# Tomo5.net
KiCad netlist of a schematic drawn in EAGLE
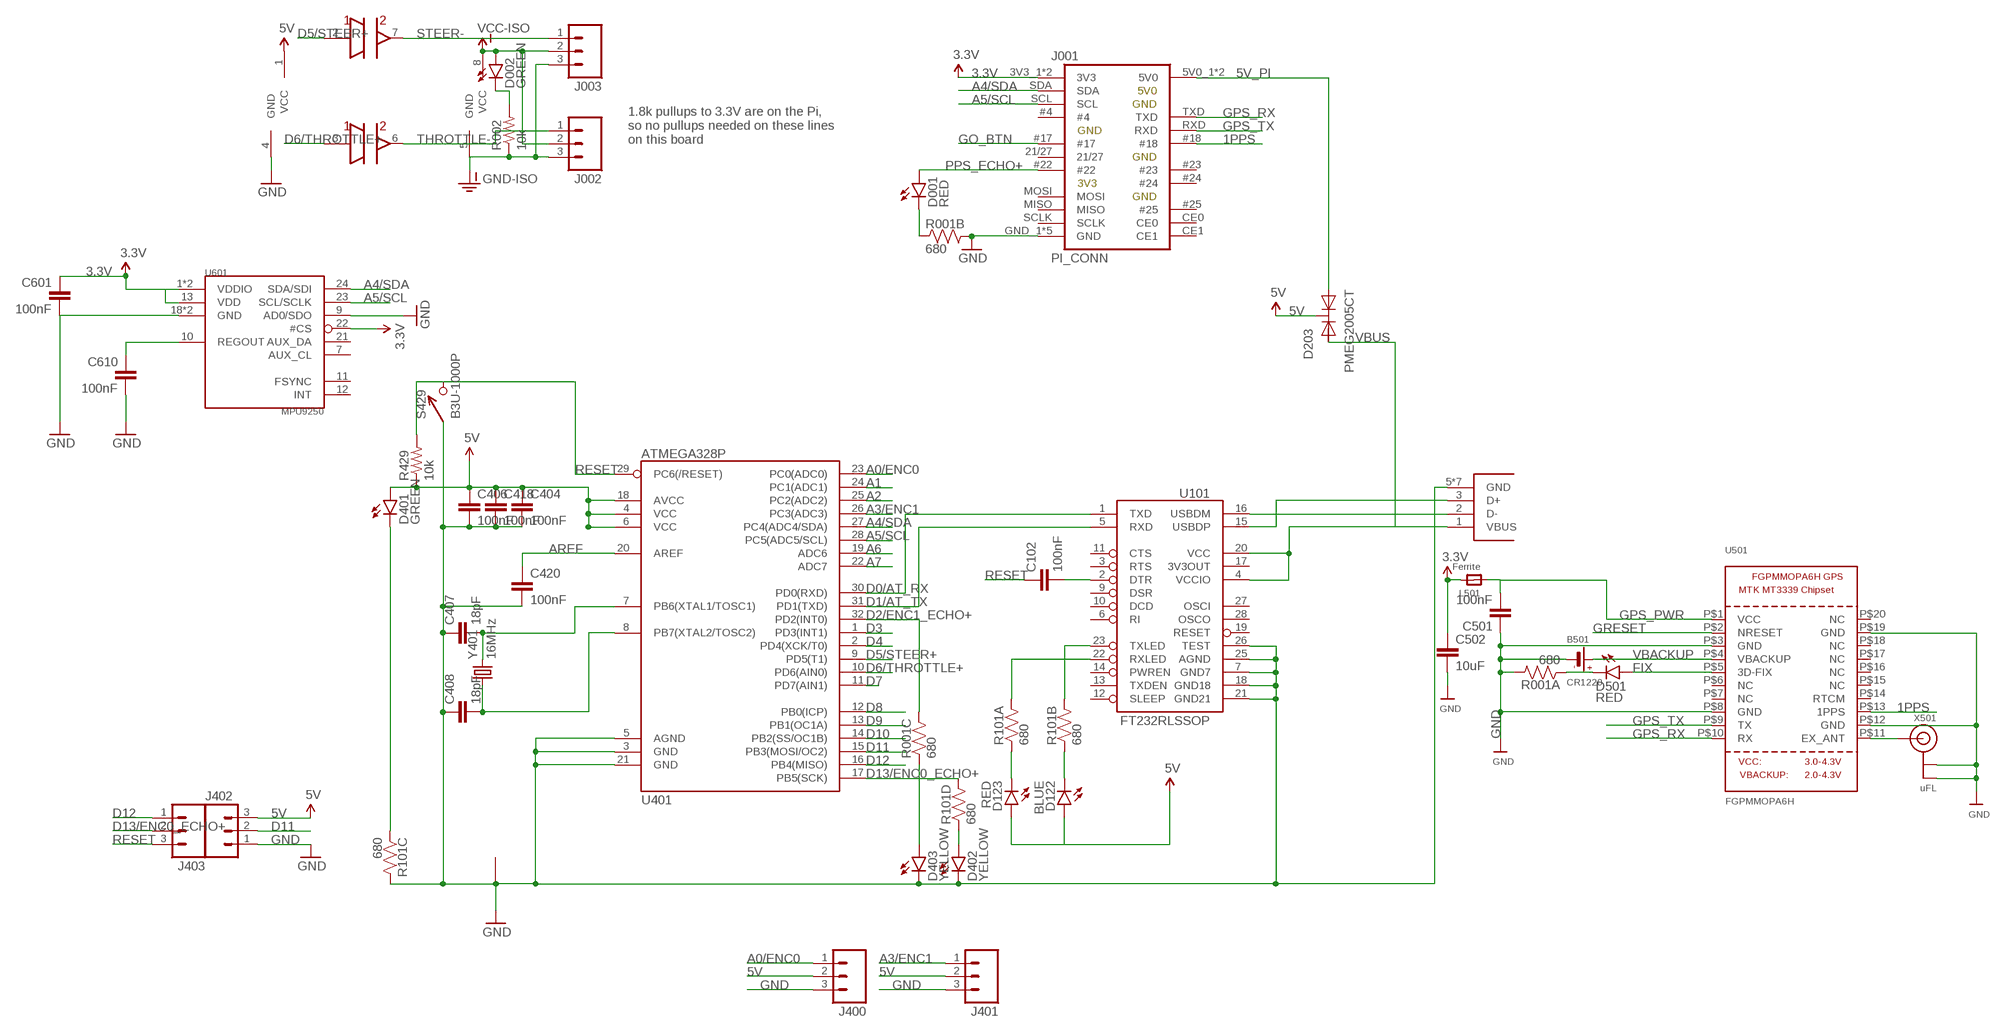
[diagram p0: schematic, sheet 1]

(export (version "E")
  (design (tool "Eeschema 10.0.6"))
  (components
    (comp (ref "B501")
      (value "CR1220")
      (footprint "eagle-import:CR1220-2")
      (libsource (lib "eagle-import") (part "BATTERYCR1220_2"))
    )
    (comp (ref "C102")
      (value "100nF")
      (footprint "eagle-import:0402-CAP")
      (libsource (lib "eagle-import") (part "CAP0402-CAP"))
    )
    (comp (ref "C404")
      (value "100nF")
      (footprint "eagle-import:0402-CAP")
      (libsource (lib "eagle-import") (part "CAP0402-CAP"))
    )
    (comp (ref "C406")
      (value "100nF")
      (footprint "eagle-import:0402-CAP")
      (libsource (lib "eagle-import") (part "CAP0402-CAP"))
    )
    (comp (ref "C407")
      (value "18pF")
      (footprint "eagle-import:0402-CAP")
      (libsource (lib "eagle-import") (part "CAP0402-CAP"))
    )
    (comp (ref "C408")
      (value "18pF")
      (footprint "eagle-import:0402-CAP")
      (libsource (lib "eagle-import") (part "CAP0402-CAP"))
    )
    (comp (ref "C418")
      (value "100nF")
      (footprint "eagle-import:0402-CAP")
      (libsource (lib "eagle-import") (part "CAP0402-CAP"))
    )
    (comp (ref "C420")
      (value "100nF")
      (footprint "eagle-import:0402-CAP")
      (libsource (lib "eagle-import") (part "CAP0402-CAP"))
    )
    (comp (ref "C501")
      (value "100nF")
      (footprint "eagle-import:0402-CAP")
      (libsource (lib "eagle-import") (part "CAP0402-CAP"))
    )
    (comp (ref "C502")
      (value "10uF")
      (footprint "eagle-import:1206")
      (libsource (lib "eagle-import") (part "SparkFun-Capacitors_CAP1206"))
    )
    (comp (ref "C601")
      (value "100nF")
      (footprint "eagle-import:0603-CAP")
      (libsource (lib "eagle-import") (part "0.1UF-25V(+80/-20%)(0603)"))
    )
    (comp (ref "C610")
      (value "100nF")
      (footprint "eagle-import:0402-CAP")
      (libsource (lib "eagle-import") (part "SparkFun-Capacitors_CAP0402-CAP"))
    )
    (comp (ref "D001")
      (value "RED")
      (footprint "eagle-import:LED-0603")
      (libsource (lib "eagle-import") (part "LED0603"))
    )
    (comp (ref "D002")
      (value "GREEN")
      (footprint "eagle-import:LED-0603")
      (libsource (lib "eagle-import") (part "LED0603"))
    )
    (comp (ref "D122")
      (value "BLUE")
      (footprint "eagle-import:LED-0603")
      (libsource (lib "eagle-import") (part "LED0603"))
    )
    (comp (ref "D123")
      (value "RED")
      (footprint "eagle-import:LED-0603")
      (libsource (lib "eagle-import") (part "LED0603"))
    )
    (comp (ref "D203")
      (value "PMEG2005CT")
      (footprint "eagle-import:SOT-23-3")
      (libsource (lib "eagle-import") (part "DIODE_COMMON_CATHODEPMEG2005CT"))
    )
    (comp (ref "D401")
      (value "GREEN")
      (footprint "eagle-import:LED-0603")
      (libsource (lib "eagle-import") (part "LED0603"))
    )
    (comp (ref "D402")
      (value "YELLOW")
      (footprint "eagle-import:LED-0603")
      (libsource (lib "eagle-import") (part "LED0603"))
    )
    (comp (ref "D403")
      (value "YELLOW")
      (footprint "eagle-import:LED-0603")
      (libsource (lib "eagle-import") (part "LED0603"))
    )
    (comp (ref "D501")
      (value "RED")
      (footprint "eagle-import:LED-0603")
      (libsource (lib "eagle-import") (part "LED0603"))
    )
    (comp (ref "J001")
      (value "PI_CONN")
      (footprint "eagle-import:PI_CONN")
      (libsource (lib "eagle-import") (part "PI_CONN"))
    )
    (comp (ref "J002")
      (value "M03PTH")
      (footprint "eagle-import:1X03")
      (libsource (lib "eagle-import") (part "M03PTH"))
    )
    (comp (ref "J003")
      (value "M03PTH")
      (footprint "eagle-import:1X03")
      (libsource (lib "eagle-import") (part "M03PTH"))
    )
    (comp (ref "J101")
      (value "USB_MICROB_JST")
      (footprint "eagle-import:UB-MC5BR3-SD204-4S")
      (libsource (lib "eagle-import") (part "USB_MICROB_JST"))
    )
    (comp (ref "J400")
      (value "M03PTH")
      (footprint "eagle-import:1X03")
      (libsource (lib "eagle-import") (part "M03PTH"))
    )
    (comp (ref "J401")
      (value "M03PTH")
      (footprint "eagle-import:1X03")
      (libsource (lib "eagle-import") (part "M03PTH"))
    )
    (comp (ref "J402")
      (value "M03PTH")
      (footprint "eagle-import:1X03")
      (libsource (lib "eagle-import") (part "M03PTH"))
    )
    (comp (ref "J403")
      (value "M03PTH")
      (footprint "eagle-import:1X03")
      (libsource (lib "eagle-import") (part "M03PTH"))
    )
    (comp (ref "L501")
      (value "Ferrite")
      (footprint "eagle-import:0805-NO")
      (libsource (lib "eagle-import") (part "FERRITE-0805NO"))
    )
    (comp (ref "R001")
      (value "680")
      (footprint "eagle-import:CRA04")
      (fields (field (name "DIGIKEY") "CRA4S8680CT-ND"))
      (libsource (lib "eagle-import") (part "RP404"))
    )
    (comp (ref "R002")
      (value "10k")
      (footprint "eagle-import:0402-RES")
      (libsource (lib "eagle-import") (part "RESISTOR0402-RES"))
    )
    (comp (ref "R101")
      (value "680")
      (footprint "eagle-import:CRA04")
      (fields (field (name "DIGIKEY") "CRA4S8680CT-ND"))
      (libsource (lib "eagle-import") (part "RP404"))
    )
    (comp (ref "R429")
      (value "10k")
      (footprint "eagle-import:0402-RES")
      (libsource (lib "eagle-import") (part "RESISTOR0402-RES"))
    )
    (comp (ref "S429")
      (value "B3U-1000P")
      (footprint "eagle-import:B3U-1000P")
      (libsource (lib "eagle-import") (part "B3U-1000P"))
    )
    (comp (ref "U$7")
      (value "ADUM3221")
      (footprint "eagle-import:SO8N")
      (libsource (lib "eagle-import") (part "ADUM3221"))
    )
    (comp (ref "U101")
      (value "FT232RLSSOP")
      (footprint "eagle-import:SSOP28DB")
      (libsource (lib "eagle-import") (part "FT232RLSSOP"))
    )
    (comp (ref "U401")
      (value "ATMEGA328P")
      (footprint "eagle-import:TQFP32-08")
      (libsource (lib "eagle-import") (part "ATMEGA168"))
    )
    (comp (ref "U501")
      (value "FGPMMOPA6H")
      (footprint "eagle-import:FGPMMOPA6H")
      (libsource (lib "eagle-import") (part "GPS_FGPMMOPA6H"))
    )
    (comp (ref "U601")
      (value "MPU9250")
      (footprint "eagle-import:LQFN_3MM_3MM")
      (libsource (lib "eagle-import") (part "MPU9250"))
    )
    (comp (ref "X501")
      (value "uFL")
      (footprint "eagle-import:U.FL")
      (libsource (lib "eagle-import") (part "ANTENNA_U.FL"))
    )
    (comp (ref "Y401")
      (value "16MHz")
      (footprint "eagle-import:CRYSTAL_SMD_2MM_2_5MM")
      (fields (field (name "DIGIKEY") "478-6955-1-ND"))
      (libsource (lib "eagle-import") (part "CX2520"))
    )
  )
  (nets
    (net (code "1") (name "/1PPS") (class "Default")
      (node (ref "J001") (pin "#18") (pinfunction "#18_#18") (pintype "passive"))
      (node (ref "U501") (pin "P$13") (pinfunction "1PPS_P$13") (pintype "bidirectional"))
    )
    (net (code "2") (name "/5V_PI") (class "Default")
      (node (ref "D203") (pin "1") (pinfunction "A1_1") (pintype "passive"))
      (node (ref "J001") (pin "5V0_1") (pinfunction "5V0_5V0_1") (pintype "passive"))
      (node (ref "J001") (pin "5V0_2") (pinfunction "5V0_5V0_2") (pintype "passive"))
    )
    (net (code "3") (name "/A0{slash}ENC0") (class "Default")
      (node (ref "J400") (pin "1") (pinfunction "1_1") (pintype "passive"))
      (node (ref "U401") (pin "23") (pinfunction "PC0(ADC0)_23") (pintype "bidirectional"))
    )
    (net (code "4") (name "/A1") (class "Default")
      (node (ref "U401") (pin "24") (pinfunction "PC1(ADC1)_24") (pintype "bidirectional"))
    )
    (net (code "5") (name "/A2") (class "Default")
      (node (ref "U401") (pin "25") (pinfunction "PC2(ADC2)_25") (pintype "bidirectional"))
    )
    (net (code "6") (name "/A3{slash}ENC1") (class "Default")
      (node (ref "J401") (pin "1") (pinfunction "1_1") (pintype "passive"))
      (node (ref "U401") (pin "26") (pinfunction "PC3(ADC3)_26") (pintype "bidirectional"))
    )
    (net (code "7") (name "/A4{slash}SDA") (class "Default")
      (node (ref "J001") (pin "SDA") (pinfunction "SDA_SDA") (pintype "passive"))
      (node (ref "U401") (pin "27") (pinfunction "PC4(ADC4/SDA)_27") (pintype "bidirectional"))
      (node (ref "U601") (pin "24") (pinfunction "SDA/SDI_24") (pintype "bidirectional"))
    )
    (net (code "8") (name "/A5{slash}SCL") (class "Default")
      (node (ref "J001") (pin "SCL") (pinfunction "SCL_SCL") (pintype "passive"))
      (node (ref "U401") (pin "28") (pinfunction "PC5(ADC5/SCL)_28") (pintype "bidirectional"))
      (node (ref "U601") (pin "23") (pinfunction "SCL/SCLK_23") (pintype "bidirectional"))
    )
    (net (code "9") (name "/A6") (class "Default")
      (node (ref "U401") (pin "19") (pinfunction "ADC6_19") (pintype "bidirectional"))
    )
    (net (code "10") (name "/A7") (class "Default")
      (node (ref "U401") (pin "22") (pinfunction "ADC7_22") (pintype "bidirectional"))
    )
    (net (code "11") (name "/AREF") (class "Default")
      (node (ref "C420") (pin "1") (pinfunction "1_1") (pintype "passive"))
      (node (ref "U401") (pin "20") (pinfunction "AREF_20") (pintype "bidirectional"))
    )
    (net (code "12") (name "/D0{slash}AT_RX") (class "Default")
      (node (ref "U101") (pin "1") (pinfunction "TXD_1") (pintype "output"))
      (node (ref "U401") (pin "30") (pinfunction "PD0(RXD)_30") (pintype "bidirectional"))
    )
    (net (code "13") (name "/D1{slash}AT_TX") (class "Default")
      (node (ref "U101") (pin "5") (pinfunction "RXD_5") (pintype "input"))
      (node (ref "U401") (pin "31") (pinfunction "PD1(TXD)_31") (pintype "bidirectional"))
    )
    (net (code "14") (name "/D2{slash}ENC1_ECHO+") (class "Default")
      (node (ref "R001") (pin "6") (pinfunction "2_6") (pintype "passive"))
      (node (ref "U401") (pin "32") (pinfunction "PD2(INT0)_32") (pintype "bidirectional"))
    )
    (net (code "15") (name "/D3") (class "Default")
      (node (ref "U401") (pin "1") (pinfunction "PD3(INT1)_1") (pintype "bidirectional"))
    )
    (net (code "16") (name "/D4") (class "Default")
      (node (ref "U401") (pin "2") (pinfunction "PD4(XCK/T0)_2") (pintype "bidirectional"))
    )
    (net (code "17") (name "/D5{slash}STEER+") (class "Default")
      (node (ref "U$7") (pin "2") (pinfunction "IN_2") (pintype "input"))
      (node (ref "U401") (pin "9") (pinfunction "PD5(T1)_9") (pintype "bidirectional"))
    )
    (net (code "18") (name "/D6{slash}THROTTLE+") (class "Default")
      (node (ref "U$7") (pin "3") (pinfunction "IN_3") (pintype "input"))
      (node (ref "U401") (pin "10") (pinfunction "PD6(AIN0)_10") (pintype "bidirectional"))
    )
    (net (code "19") (name "/D7") (class "Default")
      (node (ref "U401") (pin "11") (pinfunction "PD7(AIN1)_11") (pintype "bidirectional"))
    )
    (net (code "20") (name "/D8") (class "Default")
      (node (ref "U401") (pin "12") (pinfunction "PB0(ICP)_12") (pintype "bidirectional"))
    )
    (net (code "21") (name "/D9") (class "Default")
      (node (ref "U401") (pin "13") (pinfunction "PB1(OC1A)_13") (pintype "bidirectional"))
    )
    (net (code "22") (name "/D10") (class "Default")
      (node (ref "U401") (pin "14") (pinfunction "PB2(SS/OC1B)_14") (pintype "bidirectional"))
    )
    (net (code "23") (name "/D11") (class "Default")
      (node (ref "J402") (pin "2") (pinfunction "2_2") (pintype "passive"))
      (node (ref "U401") (pin "15") (pinfunction "PB3(MOSI/OC2)_15") (pintype "bidirectional"))
    )
    (net (code "24") (name "/D12") (class "Default")
      (node (ref "J403") (pin "1") (pinfunction "1_1") (pintype "passive"))
      (node (ref "U401") (pin "16") (pinfunction "PB4(MISO)_16") (pintype "bidirectional"))
    )
    (net (code "25") (name "/D13{slash}ENC0_ECHO+") (class "Default")
      (node (ref "J403") (pin "2") (pinfunction "2_2") (pintype "passive"))
      (node (ref "R101") (pin "5") (pinfunction "2_5") (pintype "passive"))
      (node (ref "U401") (pin "17") (pinfunction "PB5(SCK)_17") (pintype "bidirectional"))
    )
    (net (code "26") (name "/FIX") (class "Default")
      (node (ref "D501") (pin "A") (pinfunction "A_A") (pintype "passive"))
      (node (ref "U501") (pin "P$5") (pinfunction "3D-FIX_P$5") (pintype "bidirectional"))
    )
    (net (code "27") (name "/GO_BTN") (class "Default")
      (node (ref "J001") (pin "#17") (pinfunction "#17_#17") (pintype "passive"))
    )
    (net (code "28") (name "/GPS_PWR") (class "Default")
      (node (ref "C501") (pin "2") (pinfunction "2_2") (pintype "passive"))
      (node (ref "L501") (pin "1") (pinfunction "P$1_1") (pintype "passive"))
      (node (ref "U501") (pin "P$1") (pinfunction "VCC_P$1") (pintype "bidirectional"))
    )
    (net (code "29") (name "/GPS_RX") (class "Default")
      (node (ref "J001") (pin "TXD") (pinfunction "TXD_TXD") (pintype "passive"))
      (node (ref "U501") (pin "P$10") (pinfunction "RX_P$10") (pintype "bidirectional"))
    )
    (net (code "30") (name "/GPS_TX") (class "Default")
      (node (ref "J001") (pin "RXD") (pinfunction "RXD_RXD") (pintype "passive"))
      (node (ref "U501") (pin "P$9") (pinfunction "TX_P$9") (pintype "bidirectional"))
    )
    (net (code "31") (name "/GRESET") (class "Default")
      (node (ref "U501") (pin "P$2") (pinfunction "NRESET_P$2") (pintype "bidirectional"))
    )
    (net (code "32") (name "/PPS_ECHO+") (class "Default")
      (node (ref "D001") (pin "A") (pinfunction "A_A") (pintype "passive"))
      (node (ref "J001") (pin "#22") (pinfunction "#22_#22") (pintype "passive"))
    )
    (net (code "33") (name "/RESET") (class "Default")
      (node (ref "C102") (pin "1") (pinfunction "1_1") (pintype "passive"))
      (node (ref "J403") (pin "3") (pinfunction "3_3") (pintype "passive"))
      (node (ref "R429") (pin "2") (pinfunction "2_2") (pintype "passive"))
      (node (ref "S429") (pin "P$2") (pinfunction "2_P$2") (pintype "bidirectional"))
      (node (ref "U401") (pin "29") (pinfunction "PC6(/RESET)_29") (pintype "bidirectional"))
    )
    (net (code "34") (name "/STEER-") (class "Default")
      (node (ref "J003") (pin "1") (pinfunction "1_1") (pintype "passive"))
      (node (ref "U$7") (pin "7") (pinfunction "OUT_7") (pintype "bidirectional"))
    )
    (net (code "35") (name "/THROTTLE-") (class "Default")
      (node (ref "J002") (pin "1") (pinfunction "1_1") (pintype "passive"))
      (node (ref "U$7") (pin "6") (pinfunction "OUT_6") (pintype "bidirectional"))
    )
    (net (code "36") (name "/VBACKUP") (class "Default")
      (node (ref "B501") (pin "+") (pinfunction "+_+") (pintype "passive"))
      (node (ref "U501") (pin "P$4") (pinfunction "VBACKUP_P$4") (pintype "bidirectional"))
    )
    (net (code "37") (name "/VBUS") (class "Default")
      (node (ref "D203") (pin "2") (pinfunction "A2_2") (pintype "passive"))
      (node (ref "J101") (pin "1") (pinfunction "VBUS_1") (pintype "bidirectional"))
      (node (ref "U101") (pin "20") (pinfunction "VCC_20") (pintype "power_in"))
      (node (ref "U101") (pin "4") (pinfunction "VCCIO_4") (pintype "power_in"))
    )
    (net (code "38") (name "3.3V") (class "Default")
      (node (ref "C502") (pin "1") (pinfunction "1_1") (pintype "passive"))
      (node (ref "C601") (pin "1") (pinfunction "1_1") (pintype "passive"))
      (node (ref "J001") (pin "3V3_1") (pinfunction "3V3_3V3_1") (pintype "passive"))
      (node (ref "J001") (pin "3V3_2") (pinfunction "3V3_3V3_2") (pintype "passive"))
      (node (ref "L501") (pin "2") (pinfunction "P$2_2") (pintype "passive"))
      (node (ref "U601") (pin "1") (pinfunction "VDDIO_1") (pintype "bidirectional"))
      (node (ref "U601") (pin "13") (pinfunction "VDD_13") (pintype "bidirectional"))
      (node (ref "U601") (pin "22") (pinfunction "#CS_22") (pintype "bidirectional"))
      (node (ref "U601") (pin "8") (pinfunction "VDDIO_8") (pintype "bidirectional"))
    )
    (net (code "39") (name "5V") (class "Default")
      (node (ref "C404") (pin "1") (pinfunction "1_1") (pintype "passive"))
      (node (ref "C406") (pin "1") (pinfunction "1_1") (pintype "passive"))
      (node (ref "C418") (pin "1") (pinfunction "1_1") (pintype "passive"))
      (node (ref "D122") (pin "A") (pinfunction "A_A") (pintype "passive"))
      (node (ref "D123") (pin "A") (pinfunction "A_A") (pintype "passive"))
      (node (ref "D203") (pin "3") (pinfunction "K_3") (pintype "passive"))
      (node (ref "D401") (pin "A") (pinfunction "A_A") (pintype "passive"))
      (node (ref "J400") (pin "2") (pinfunction "2_2") (pintype "passive"))
      (node (ref "J401") (pin "2") (pinfunction "2_2") (pintype "passive"))
      (node (ref "J402") (pin "3") (pinfunction "3_3") (pintype "passive"))
      (node (ref "R429") (pin "1") (pinfunction "1_1") (pintype "passive"))
      (node (ref "U$7") (pin "1") (pinfunction "VCC_1") (pintype "bidirectional"))
      (node (ref "U401") (pin "18") (pinfunction "AVCC_18") (pintype "bidirectional"))
      (node (ref "U401") (pin "4") (pinfunction "VCC_4") (pintype "bidirectional"))
      (node (ref "U401") (pin "6") (pinfunction "VCC_6") (pintype "bidirectional"))
    )
    (net (code "40") (name "GND") (class "Default")
      (node (ref "B501") (pin "-") (pinfunction "-_-") (pintype "passive"))
      (node (ref "C404") (pin "2") (pinfunction "2_2") (pintype "passive"))
      (node (ref "C406") (pin "2") (pinfunction "2_2") (pintype "passive"))
      (node (ref "C407") (pin "1") (pinfunction "1_1") (pintype "passive"))
      (node (ref "C408") (pin "1") (pinfunction "1_1") (pintype "passive"))
      (node (ref "C418") (pin "2") (pinfunction "2_2") (pintype "passive"))
      (node (ref "C420") (pin "2") (pinfunction "2_2") (pintype "passive"))
      (node (ref "C501") (pin "1") (pinfunction "1_1") (pintype "passive"))
      (node (ref "C502") (pin "2") (pinfunction "2_2") (pintype "passive"))
      (node (ref "C601") (pin "2") (pinfunction "2_2") (pintype "passive"))
      (node (ref "C610") (pin "2") (pinfunction "2_2") (pintype "passive"))
      (node (ref "D402") (pin "C") (pinfunction "C_C") (pintype "passive"))
      (node (ref "D403") (pin "C") (pinfunction "C_C") (pintype "passive"))
      (node (ref "J001") (pin "GND_1") (pinfunction "GND_GND_1") (pintype "passive"))
      (node (ref "J001") (pin "GND_2") (pinfunction "GND_GND_2") (pintype "passive"))
      (node (ref "J001") (pin "GND_3") (pinfunction "GND_GND_3") (pintype "passive"))
      (node (ref "J001") (pin "GND_4") (pinfunction "GND_GND_4") (pintype "passive"))
      (node (ref "J001") (pin "GND_5") (pinfunction "GND_GND_5") (pintype "passive"))
      (node (ref "J101") (pin "5") (pinfunction "GND_5") (pintype "bidirectional"))
      (node (ref "J101") (pin "P$10") (pinfunction "GND_P$10") (pintype "bidirectional"))
      (node (ref "J101") (pin "P$11") (pinfunction "GND_P$11") (pintype "bidirectional"))
      (node (ref "J101") (pin "P$6") (pinfunction "GND_P$6") (pintype "bidirectional"))
      (node (ref "J101") (pin "P$7") (pinfunction "GND_P$7") (pintype "bidirectional"))
      (node (ref "J101") (pin "P$8") (pinfunction "GND_P$8") (pintype "bidirectional"))
      (node (ref "J101") (pin "P$9") (pinfunction "GND_P$9") (pintype "bidirectional"))
      (node (ref "J400") (pin "3") (pinfunction "3_3") (pintype "passive"))
      (node (ref "J401") (pin "3") (pinfunction "3_3") (pintype "passive"))
      (node (ref "J402") (pin "1") (pinfunction "1_1") (pintype "passive"))
      (node (ref "R001") (pin "7") (pinfunction "2_7") (pintype "passive"))
      (node (ref "R001") (pin "8") (pinfunction "2_8") (pintype "passive"))
      (node (ref "R101") (pin "6") (pinfunction "2_6") (pintype "passive"))
      (node (ref "S429") (pin "P$1") (pinfunction "1_P$1") (pintype "bidirectional"))
      (node (ref "U$7") (pin "4") (pinfunction "GND_4") (pintype "bidirectional"))
      (node (ref "U101") (pin "18") (pinfunction "GND18_18") (pintype "power_in"))
      (node (ref "U101") (pin "21") (pinfunction "GND21_21") (pintype "power_in"))
      (node (ref "U101") (pin "25") (pinfunction "AGND_25") (pintype "power_in"))
      (node (ref "U101") (pin "26") (pinfunction "TEST_26") (pintype "input"))
      (node (ref "U101") (pin "7") (pinfunction "GND7_7") (pintype "power_in"))
      (node (ref "U401") (pin "21") (pinfunction "GND_21") (pintype "bidirectional"))
      (node (ref "U401") (pin "3") (pinfunction "GND_3") (pintype "bidirectional"))
      (node (ref "U401") (pin "5") (pinfunction "AGND_5") (pintype "bidirectional"))
      (node (ref "U501") (pin "P$12") (pinfunction "GND_P$12") (pintype "bidirectional"))
      (node (ref "U501") (pin "P$19") (pinfunction "GND_P$19") (pintype "bidirectional"))
      (node (ref "U501") (pin "P$3") (pinfunction "GND_P$3") (pintype "bidirectional"))
      (node (ref "U501") (pin "P$8") (pinfunction "GND_P$8") (pintype "bidirectional"))
      (node (ref "U601") (pin "18") (pinfunction "GND_18") (pintype "bidirectional"))
      (node (ref "U601") (pin "20") (pinfunction "GND_20") (pintype "bidirectional"))
      (node (ref "U601") (pin "9") (pinfunction "AD0/SDO_9") (pintype "bidirectional"))
      (node (ref "X501") (pin "1") (pinfunction "GND_1") (pintype "passive"))
      (node (ref "X501") (pin "2") (pinfunction "GND_2") (pintype "passive"))
      (node (ref "Y401") (pin "2") (pinfunction "1_2") (pintype "bidirectional"))
      (node (ref "Y401") (pin "4") (pinfunction "1_4") (pintype "bidirectional"))
    )
    (net (code "41") (name "GND-ISO") (class "Default")
      (node (ref "J002") (pin "3") (pinfunction "3_3") (pintype "passive"))
      (node (ref "J003") (pin "3") (pinfunction "3_3") (pintype "passive"))
      (node (ref "R002") (pin "1") (pinfunction "1_1") (pintype "passive"))
      (node (ref "U$7") (pin "5") (pinfunction "GND_5") (pintype "bidirectional"))
    )
    (net (code "42") (name "Net-(D002-PadC)") (class "Default")
      (node (ref "D002") (pin "C") (pinfunction "C_C") (pintype "passive"))
      (node (ref "R002") (pin "2") (pinfunction "2_2") (pintype "passive"))
    )
    (net (code "43") (name "Net-(D123-PadC)") (class "Default")
      (node (ref "D123") (pin "C") (pinfunction "C_C") (pintype "passive"))
      (node (ref "R101") (pin "1") (pinfunction "1_1") (pintype "passive"))
    )
    (net (code "44") (name "Net-(D501-PadC)") (class "Default")
      (node (ref "D501") (pin "C") (pinfunction "C_C") (pintype "passive"))
      (node (ref "R001") (pin "1") (pinfunction "1_1") (pintype "passive"))
    )
    (net (code "45") (name "Net-(J101-D+)") (class "Default")
      (node (ref "J101") (pin "3") (pinfunction "D+_3") (pintype "bidirectional"))
      (node (ref "U101") (pin "15") (pinfunction "USBDP_15") (pintype "bidirectional"))
    )
    (net (code "46") (name "Net-(J101-D-)") (class "Default")
      (node (ref "J101") (pin "2") (pinfunction "D-_2") (pintype "bidirectional"))
      (node (ref "U101") (pin "16") (pinfunction "USBDM_16") (pintype "bidirectional"))
    )
    (net (code "47") (name "Net-(R001B-1)") (class "Default")
      (node (ref "D001") (pin "C") (pinfunction "C_C") (pintype "passive"))
      (node (ref "R001") (pin "2") (pinfunction "1_2") (pintype "passive"))
    )
    (net (code "48") (name "Net-(R001C-1)") (class "Default")
      (node (ref "D403") (pin "A") (pinfunction "A_A") (pintype "passive"))
      (node (ref "R001") (pin "3") (pinfunction "1_3") (pintype "passive"))
    )
    (net (code "49") (name "Net-(R101A-2)") (class "Default")
      (node (ref "R101") (pin "8") (pinfunction "2_8") (pintype "passive"))
      (node (ref "U101") (pin "22") (pinfunction "RXLED_22") (pintype "input"))
    )
    (net (code "50") (name "Net-(R101B-1)") (class "Default")
      (node (ref "D122") (pin "C") (pinfunction "C_C") (pintype "passive"))
      (node (ref "R101") (pin "2") (pinfunction "1_2") (pintype "passive"))
    )
    (net (code "51") (name "Net-(R101B-2)") (class "Default")
      (node (ref "R101") (pin "7") (pinfunction "2_7") (pintype "passive"))
      (node (ref "U101") (pin "23") (pinfunction "TXLED_23") (pintype "input"))
    )
    (net (code "52") (name "Net-(R101C-1)") (class "Default")
      (node (ref "D401") (pin "C") (pinfunction "C_C") (pintype "passive"))
      (node (ref "R101") (pin "3") (pinfunction "1_3") (pintype "passive"))
    )
    (net (code "53") (name "Net-(R101D-1)") (class "Default")
      (node (ref "D402") (pin "A") (pinfunction "A_A") (pintype "passive"))
      (node (ref "R101") (pin "4") (pinfunction "1_4") (pintype "passive"))
    )
    (net (code "54") (name "Net-(U101-DTR)") (class "Default")
      (node (ref "C102") (pin "2") (pinfunction "2_2") (pintype "passive"))
      (node (ref "U101") (pin "2") (pinfunction "DTR_2") (pintype "output"))
    )
    (net (code "55") (name "Net-(U401-PB6(XTAL1{slash}TOSC1))") (class "Default")
      (node (ref "C407") (pin "2") (pinfunction "2_2") (pintype "passive"))
      (node (ref "U401") (pin "7") (pinfunction "PB6(XTAL1/TOSC1)_7") (pintype "bidirectional"))
      (node (ref "Y401") (pin "3") (pinfunction "2_3") (pintype "passive"))
    )
    (net (code "56") (name "Net-(U401-PB7(XTAL2{slash}TOSC2))") (class "Default")
      (node (ref "C408") (pin "2") (pinfunction "2_2") (pintype "passive"))
      (node (ref "U401") (pin "8") (pinfunction "PB7(XTAL2/TOSC2)_8") (pintype "bidirectional"))
      (node (ref "Y401") (pin "1") (pinfunction "1_1") (pintype "passive"))
    )
    (net (code "57") (name "Net-(U501-EX_ANT)") (class "Default")
      (node (ref "U501") (pin "P$11") (pinfunction "EX_ANT_P$11") (pintype "bidirectional"))
      (node (ref "X501") (pin "3") (pinfunction "SIGNAL_3") (pintype "passive"))
    )
    (net (code "58") (name "Net-(U601-REGOUT)") (class "Default")
      (node (ref "C610") (pin "1") (pinfunction "1_1") (pintype "passive"))
      (node (ref "U601") (pin "10") (pinfunction "REGOUT_10") (pintype "bidirectional"))
    )
    (net (code "59") (name "VCC-ISO") (class "Default")
      (node (ref "D002") (pin "A") (pinfunction "A_A") (pintype "passive"))
      (node (ref "J002") (pin "2") (pinfunction "2_2") (pintype "passive"))
      (node (ref "J003") (pin "2") (pinfunction "2_2") (pintype "passive"))
      (node (ref "U$7") (pin "8") (pinfunction "VCC_8") (pintype "bidirectional"))
    )
    (net (code "60") (name "unconnected-(J001-Pad#4)") (class "Default")
      (node (ref "J001") (pin "#4") (pinfunction "#4_#4") (pintype "passive"))
    )
    (net (code "61") (name "unconnected-(J001-Pad#23)") (class "Default")
      (node (ref "J001") (pin "#23") (pinfunction "#23_#23") (pintype "passive"))
    )
    (net (code "62") (name "unconnected-(J001-Pad#24)") (class "Default")
      (node (ref "J001") (pin "#24") (pinfunction "#24_#24") (pintype "passive"))
    )
    (net (code "63") (name "unconnected-(J001-Pad#25)") (class "Default")
      (node (ref "J001") (pin "#25") (pinfunction "#25_#25") (pintype "passive"))
    )
    (net (code "64") (name "unconnected-(J001-Pad21{slash}27)") (class "Default")
      (node (ref "J001") (pin "21/27") (pinfunction "21/27_21/27") (pintype "passive"))
    )
    (net (code "65") (name "unconnected-(J001-PadCE0)") (class "Default")
      (node (ref "J001") (pin "CE0") (pinfunction "CE0_CE0") (pintype "passive"))
    )
    (net (code "66") (name "unconnected-(J001-PadCE1)") (class "Default")
      (node (ref "J001") (pin "CE1") (pinfunction "CE1_CE1") (pintype "passive"))
    )
    (net (code "67") (name "unconnected-(J001-PadMISO)") (class "Default")
      (node (ref "J001") (pin "MISO") (pinfunction "MISO_MISO") (pintype "passive"))
    )
    (net (code "68") (name "unconnected-(J001-PadMOSI)") (class "Default")
      (node (ref "J001") (pin "MOSI") (pinfunction "MOSI_MOSI") (pintype "passive"))
    )
    (net (code "69") (name "unconnected-(J001-PadSCLK)") (class "Default")
      (node (ref "J001") (pin "SCLK") (pinfunction "SCLK_SCLK") (pintype "passive"))
    )
    (net (code "70") (name "unconnected-(U101-3V3OUT-Pad17)") (class "Default")
      (node (ref "U101") (pin "17") (pinfunction "3V3OUT_17") (pintype "output"))
    )
    (net (code "71") (name "unconnected-(U101-CTS-Pad11)") (class "Default")
      (node (ref "U101") (pin "11") (pinfunction "CTS_11") (pintype "input"))
    )
    (net (code "72") (name "unconnected-(U101-DCD-Pad10)") (class "Default")
      (node (ref "U101") (pin "10") (pinfunction "DCD_10") (pintype "input"))
    )
    (net (code "73") (name "unconnected-(U101-DSR-Pad9)") (class "Default")
      (node (ref "U101") (pin "9") (pinfunction "DSR_9") (pintype "input"))
    )
    (net (code "74") (name "unconnected-(U101-OSCI-Pad27)") (class "Default")
      (node (ref "U101") (pin "27") (pinfunction "OSCI_27") (pintype "input"))
    )
    (net (code "75") (name "unconnected-(U101-OSCO-Pad28)") (class "Default")
      (node (ref "U101") (pin "28") (pinfunction "OSCO_28") (pintype "output"))
    )
    (net (code "76") (name "unconnected-(U101-PWREN-Pad14)") (class "Default")
      (node (ref "U101") (pin "14") (pinfunction "PWREN_14") (pintype "input"))
    )
    (net (code "77") (name "unconnected-(U101-RESET-Pad19)") (class "Default")
      (node (ref "U101") (pin "19") (pinfunction "RESET_19") (pintype "input"))
    )
    (net (code "78") (name "unconnected-(U101-RI-Pad6)") (class "Default")
      (node (ref "U101") (pin "6") (pinfunction "RI_6") (pintype "input"))
    )
    (net (code "79") (name "unconnected-(U101-RTS-Pad3)") (class "Default")
      (node (ref "U101") (pin "3") (pinfunction "RTS_3") (pintype "output"))
    )
    (net (code "80") (name "unconnected-(U101-SLEEP-Pad12)") (class "Default")
      (node (ref "U101") (pin "12") (pinfunction "SLEEP_12") (pintype "input"))
    )
    (net (code "81") (name "unconnected-(U101-TXDEN-Pad13)") (class "Default")
      (node (ref "U101") (pin "13") (pinfunction "TXDEN_13") (pintype "input"))
    )
    (net (code "82") (name "unconnected-(U501-NC-PadP$6)") (class "Default")
      (node (ref "U501") (pin "P$6") (pinfunction "NC_P$6") (pintype "bidirectional"))
    )
    (net (code "83") (name "unconnected-(U501-NC-PadP$7)") (class "Default")
      (node (ref "U501") (pin "P$7") (pinfunction "NC_P$7") (pintype "bidirectional"))
    )
    (net (code "84") (name "unconnected-(U501-NC-PadP$15)") (class "Default")
      (node (ref "U501") (pin "P$15") (pinfunction "NC_P$15") (pintype "bidirectional"))
    )
    (net (code "85") (name "unconnected-(U501-NC-PadP$16)") (class "Default")
      (node (ref "U501") (pin "P$16") (pinfunction "NC_P$16") (pintype "bidirectional"))
    )
    (net (code "86") (name "unconnected-(U501-NC-PadP$17)") (class "Default")
      (node (ref "U501") (pin "P$17") (pinfunction "NC_P$17") (pintype "bidirectional"))
    )
    (net (code "87") (name "unconnected-(U501-NC-PadP$18)") (class "Default")
      (node (ref "U501") (pin "P$18") (pinfunction "NC_P$18") (pintype "bidirectional"))
    )
    (net (code "88") (name "unconnected-(U501-NC-PadP$20)") (class "Default")
      (node (ref "U501") (pin "P$20") (pinfunction "NC_P$20") (pintype "bidirectional"))
    )
    (net (code "89") (name "unconnected-(U501-RTCM-PadP$14)") (class "Default")
      (node (ref "U501") (pin "P$14") (pinfunction "RTCM_P$14") (pintype "bidirectional"))
    )
    (net (code "90") (name "unconnected-(U601-AUX_CL-Pad7)") (class "Default")
      (node (ref "U601") (pin "7") (pinfunction "AUX_CL_7") (pintype "bidirectional"))
    )
    (net (code "91") (name "unconnected-(U601-AUX_DA-Pad21)") (class "Default")
      (node (ref "U601") (pin "21") (pinfunction "AUX_DA_21") (pintype "bidirectional"))
    )
    (net (code "92") (name "unconnected-(U601-FSYNC-Pad11)") (class "Default")
      (node (ref "U601") (pin "11") (pinfunction "FSYNC_11") (pintype "bidirectional"))
    )
    (net (code "93") (name "unconnected-(U601-INT-Pad12)") (class "Default")
      (node (ref "U601") (pin "12") (pinfunction "INT_12") (pintype "bidirectional"))
    )
  )
)
